# CarDelayRelay.net
KiCad netlist of a schematic drawn in EAGLE
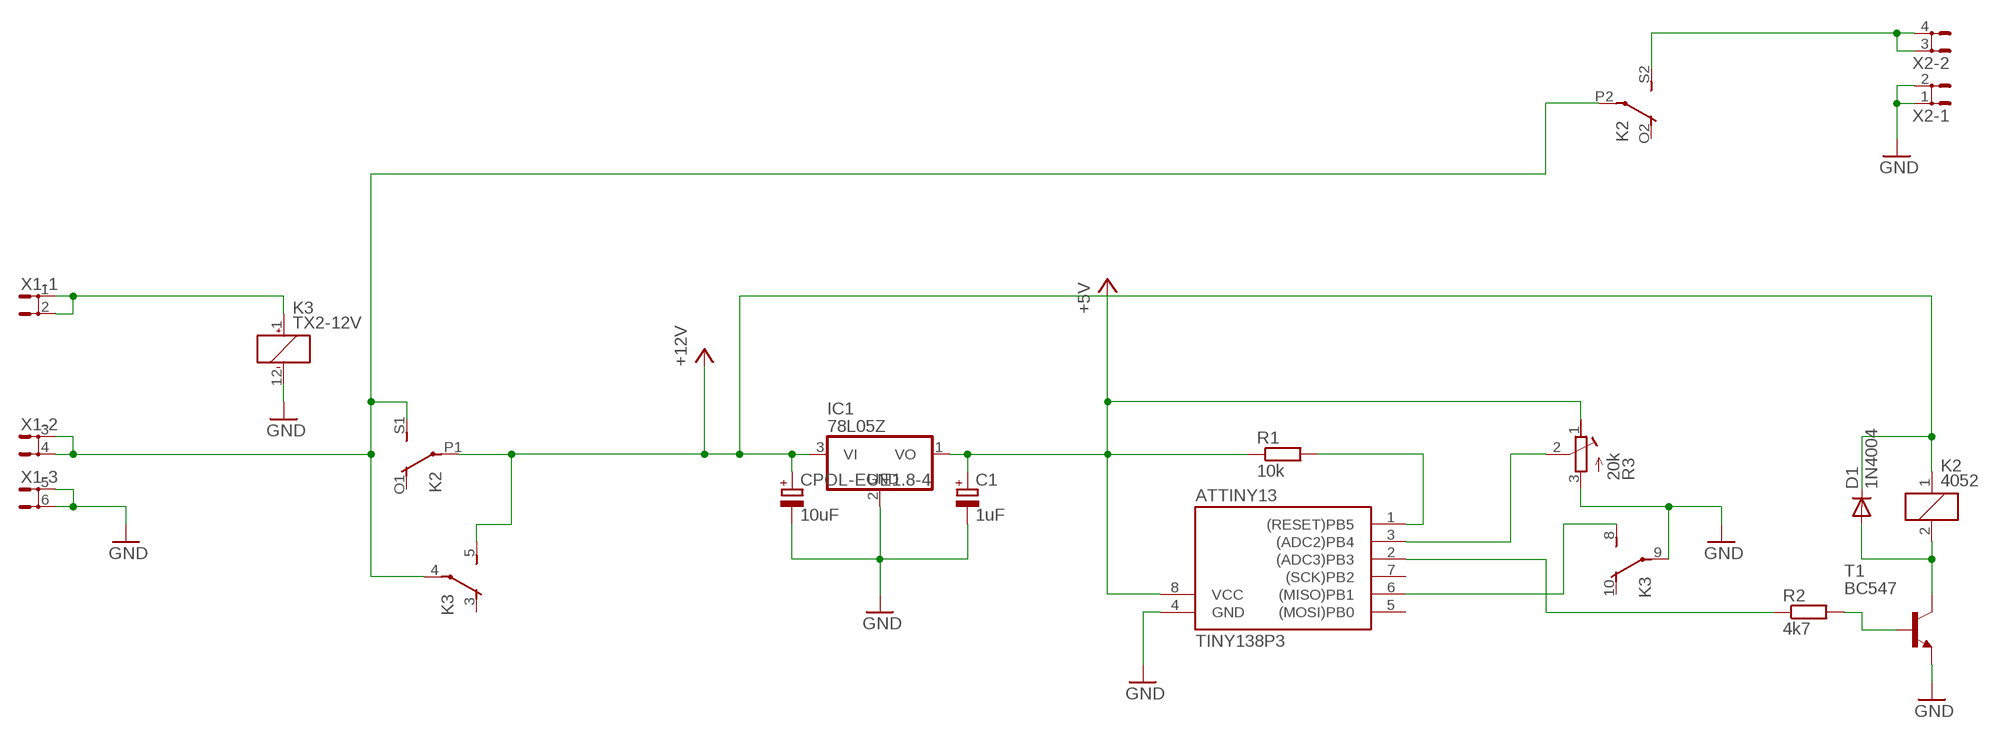
[diagram p0: schematic, sheet 1]

(export (version "E")
  (design (tool "Eeschema 10.0.6"))
  (components
    (comp (ref "ATTINY13")
      (value "TINY138P3")
      (footprint "eagle-import:DIL08")
      (libsource (lib "eagle-import") (part "TINY138P3"))
    )
    (comp (ref "C1")
      (value "1uF")
      (footprint "eagle-import:E1,8-4")
      (libsource (lib "eagle-import") (part "CPOL-EUE1.8-4"))
    )
    (comp (ref "CPOL-EUE1.8-4")
      (value "10uF")
      (footprint "eagle-import:E1,8-4")
      (libsource (lib "eagle-import") (part "CPOL-EUE1.8-4"))
    )
    (comp (ref "D1")
      (value "1N4004")
      (footprint "eagle-import:DO41-10")
      (libsource (lib "eagle-import") (part "1N4004"))
    )
    (comp (ref "IC1")
      (value "78L05Z")
      (footprint "eagle-import:TO92")
      (libsource (lib "eagle-import") (part "78ZL05"))
    )
    (comp (ref "K2")
      (value "4052")
      (footprint "eagle-import:F4052")
      (libsource (lib "eagle-import") (part "4052"))
    )
    (comp (ref "K3")
      (value "TX2-12V")
      (footprint "eagle-import:TX2")
      (fields (field (name "MF") "AROMAT/ MATSUSHITA"))
      (libsource (lib "eagle-import") (part "TX2?-12V"))
    )
    (comp (ref "R1")
      (value "10k")
      (footprint "eagle-import:0204_7")
      (libsource (lib "eagle-import") (part "R-EU_0204/7"))
    )
    (comp (ref "R2")
      (value "4k7")
      (footprint "eagle-import:0207_2V")
      (libsource (lib "eagle-import") (part "R-EU_0207/2V"))
    )
    (comp (ref "R3")
      (value "20k")
      (footprint "eagle-import:RTRIM43P")
      (libsource (lib "eagle-import") (part "R-TRIMM43P"))
    )
    (comp (ref "T1")
      (value "BC547")
      (footprint "eagle-import:TO92")
      (libsource (lib "eagle-import") (part "BC547"))
    )
    (comp (ref "X1")
      (value "SH5-3")
      (footprint "eagle-import:SH5-3")
      (libsource (lib "eagle-import") (part "SH5-3"))
    )
    (comp (ref "X2")
      (value "SH5-2")
      (footprint "eagle-import:SH5-2")
      (libsource (lib "eagle-import") (part "SH5-2"))
    )
  )
  (nets
    (net (code "1") (name "+5V") (class "Default")
      (node (ref "ATTINY13") (pin "8") (pinfunction "VCC_8") (pintype "power_in"))
      (node (ref "C1") (pin "+") (pinfunction "+_+") (pintype "passive"))
      (node (ref "IC1") (pin "1") (pinfunction "VO_1") (pintype "passive"))
      (node (ref "R1") (pin "1") (pinfunction "1_1") (pintype "passive"))
      (node (ref "R3") (pin "1") (pinfunction "A_1") (pintype "passive"))
    )
    (net (code "2") (name "+12V") (class "Default")
      (node (ref "CPOL-EUE1.8-4") (pin "+") (pinfunction "+_+") (pintype "passive"))
      (node (ref "D1") (pin "C") (pinfunction "C_C") (pintype "passive"))
      (node (ref "IC1") (pin "3") (pinfunction "VI_3") (pintype "input"))
      (node (ref "K2") (pin "1") (pinfunction "1_1") (pintype "passive"))
      (node (ref "K2") (pin "P1") (pinfunction "P_P1") (pintype "passive"))
      (node (ref "K3") (pin "5") (pinfunction "S_5") (pintype "passive"))
    )
    (net (code "3") (name "GND") (class "Default")
      (node (ref "ATTINY13") (pin "4") (pinfunction "GND_4") (pintype "power_in"))
      (node (ref "C1") (pin "-") (pinfunction "-_-") (pintype "passive"))
      (node (ref "CPOL-EUE1.8-4") (pin "-") (pinfunction "-_-") (pintype "passive"))
      (node (ref "IC1") (pin "2") (pinfunction "GND_2") (pintype "passive"))
      (node (ref "K3") (pin "12") (pinfunction "-_12") (pintype "passive"))
      (node (ref "K3") (pin "9") (pinfunction "P_9") (pintype "passive"))
      (node (ref "R3") (pin "3") (pinfunction "E_3") (pintype "passive"))
      (node (ref "T1") (pin "1") (pinfunction "E_1") (pintype "passive"))
      (node (ref "X1") (pin "5") (pinfunction "1_5") (pintype "passive"))
      (node (ref "X1") (pin "6") (pinfunction "2_6") (pintype "passive"))
      (node (ref "X2") (pin "1") (pinfunction "1_1") (pintype "passive"))
      (node (ref "X2") (pin "2") (pinfunction "2_2") (pintype "passive"))
    )
    (net (code "4") (name "Net-(ATTINY13-(ADC2)PB4)") (class "Default")
      (node (ref "ATTINY13") (pin "3") (pinfunction "(ADC2)PB4_3") (pintype "bidirectional"))
      (node (ref "R3") (pin "2") (pinfunction "S_2") (pintype "passive"))
    )
    (net (code "5") (name "Net-(ATTINY13-(ADC3)PB3)") (class "Default")
      (node (ref "ATTINY13") (pin "2") (pinfunction "(ADC3)PB3_2") (pintype "bidirectional"))
      (node (ref "R2") (pin "1") (pinfunction "1_1") (pintype "passive"))
    )
    (net (code "6") (name "Net-(ATTINY13-(MISO)PB1)") (class "Default")
      (node (ref "ATTINY13") (pin "6") (pinfunction "(MISO)PB1_6") (pintype "bidirectional"))
      (node (ref "K3") (pin "8") (pinfunction "S_8") (pintype "passive"))
    )
    (net (code "7") (name "Net-(ATTINY13-(RESET)PB5)") (class "Default")
      (node (ref "ATTINY13") (pin "1") (pinfunction "(RESET)PB5_1") (pintype "bidirectional"))
      (node (ref "R1") (pin "2") (pinfunction "2_2") (pintype "passive"))
    )
    (net (code "8") (name "Net-(K2B-S)") (class "Default")
      (node (ref "K2") (pin "P2") (pinfunction "P_P2") (pintype "passive"))
      (node (ref "K2") (pin "S1") (pinfunction "S_S1") (pintype "passive"))
      (node (ref "K3") (pin "4") (pinfunction "P_4") (pintype "passive"))
      (node (ref "X1") (pin "3") (pinfunction "1_3") (pintype "passive"))
      (node (ref "X1") (pin "4") (pinfunction "2_4") (pintype "passive"))
    )
    (net (code "9") (name "Net-(K2C-S)") (class "Default")
      (node (ref "K2") (pin "S2") (pinfunction "S_S2") (pintype "passive"))
      (node (ref "X2") (pin "3") (pinfunction "1_3") (pintype "passive"))
      (node (ref "X2") (pin "4") (pinfunction "2_4") (pintype "passive"))
    )
    (net (code "10") (name "Net-(K3C-+)") (class "Default")
      (node (ref "K3") (pin "1") (pinfunction "+_1") (pintype "passive"))
      (node (ref "X1") (pin "1") (pinfunction "1_1") (pintype "passive"))
      (node (ref "X1") (pin "2") (pinfunction "2_2") (pintype "passive"))
    )
    (net (code "11") (name "Net-(T1-B)") (class "Default")
      (node (ref "R2") (pin "2") (pinfunction "2_2") (pintype "passive"))
      (node (ref "T1") (pin "2") (pinfunction "B_2") (pintype "passive"))
    )
    (net (code "12") (name "Net-(T1-C)") (class "Default")
      (node (ref "D1") (pin "A") (pinfunction "A_A") (pintype "passive"))
      (node (ref "K2") (pin "2") (pinfunction "2_2") (pintype "passive"))
      (node (ref "T1") (pin "3") (pinfunction "C_3") (pintype "passive"))
    )
    (net (code "13") (name "unconnected-(ATTINY13-(MOSI)PB0-Pad5)") (class "Default")
      (node (ref "ATTINY13") (pin "5") (pinfunction "(MOSI)PB0_5") (pintype "bidirectional"))
    )
    (net (code "14") (name "unconnected-(ATTINY13-(SCK)PB2-Pad7)") (class "Default")
      (node (ref "ATTINY13") (pin "7") (pinfunction "(SCK)PB2_7") (pintype "bidirectional"))
    )
    (net (code "15") (name "unconnected-(K2B-O-PadO1)") (class "Default")
      (node (ref "K2") (pin "O1") (pinfunction "O_O1") (pintype "passive"))
    )
    (net (code "16") (name "unconnected-(K2C-O-PadO2)") (class "Default")
      (node (ref "K2") (pin "O2") (pinfunction "O_O2") (pintype "passive"))
    )
    (net (code "17") (name "unconnected-(K3A-O-Pad3)") (class "Default")
      (node (ref "K3") (pin "3") (pinfunction "O_3") (pintype "passive"))
    )
    (net (code "18") (name "unconnected-(K3B-O-Pad10)") (class "Default")
      (node (ref "K3") (pin "10") (pinfunction "O_10") (pintype "passive"))
    )
  )
)
